# IHM_NAV_BUTTON.net
KiCad netlist of a schematic drawn in EAGLE
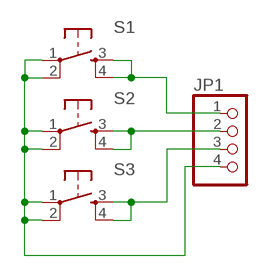
[diagram p0: schematic, sheet 1]

(export (version "E")
  (design (tool "Eeschema 10.0.6"))
  (components
    (comp (ref "JP1")
      (value "PINHD-1X04_2.54-SMD-90°")
      (footprint "eagle-import:1X04SMD_90")
      (libsource (lib "eagle-import") (part "PINHD-1X04_2.54-SMD-90°"))
    )
    (comp (ref "S1")
      (value "6MM_SWITCH6MM_SWITCH")
      (footprint "eagle-import:6MM_SWITCH")
      (libsource (lib "eagle-import") (part "6MM_SWITCH6MM_SWITCH"))
    )
    (comp (ref "S2")
      (value "6MM_SWITCH6MM_SWITCH")
      (footprint "eagle-import:6MM_SWITCH")
      (libsource (lib "eagle-import") (part "6MM_SWITCH6MM_SWITCH"))
    )
    (comp (ref "S3")
      (value "6MM_SWITCH6MM_SWITCH")
      (footprint "eagle-import:6MM_SWITCH")
      (libsource (lib "eagle-import") (part "6MM_SWITCH6MM_SWITCH"))
    )
  )
  (nets
    (net (code "1") (name "Net-(S1-P)") (class "Default")
      (node (ref "JP1") (pin "4") (pinfunction "4_4") (pintype "passive"))
      (node (ref "S1") (pin "1") (pinfunction "P_1") (pintype "passive"))
      (node (ref "S1") (pin "2") (pinfunction "P1_2") (pintype "passive"))
      (node (ref "S2") (pin "1") (pinfunction "P_1") (pintype "passive"))
      (node (ref "S2") (pin "2") (pinfunction "P1_2") (pintype "passive"))
      (node (ref "S3") (pin "1") (pinfunction "P_1") (pintype "passive"))
      (node (ref "S3") (pin "2") (pinfunction "P1_2") (pintype "passive"))
    )
    (net (code "2") (name "Net-(S1-S)") (class "Default")
      (node (ref "JP1") (pin "1") (pinfunction "1_1") (pintype "passive"))
      (node (ref "S1") (pin "3") (pinfunction "S_3") (pintype "passive"))
      (node (ref "S1") (pin "4") (pinfunction "S1_4") (pintype "passive"))
    )
    (net (code "3") (name "Net-(S2-S)") (class "Default")
      (node (ref "JP1") (pin "2") (pinfunction "2_2") (pintype "passive"))
      (node (ref "S2") (pin "3") (pinfunction "S_3") (pintype "passive"))
      (node (ref "S2") (pin "4") (pinfunction "S1_4") (pintype "passive"))
    )
    (net (code "4") (name "Net-(S3-S)") (class "Default")
      (node (ref "JP1") (pin "3") (pinfunction "3_3") (pintype "passive"))
      (node (ref "S3") (pin "3") (pinfunction "S_3") (pintype "passive"))
      (node (ref "S3") (pin "4") (pinfunction "S1_4") (pintype "passive"))
    )
  )
)
